# Debug.net
KiCad netlist of a schematic drawn in Altium Designer
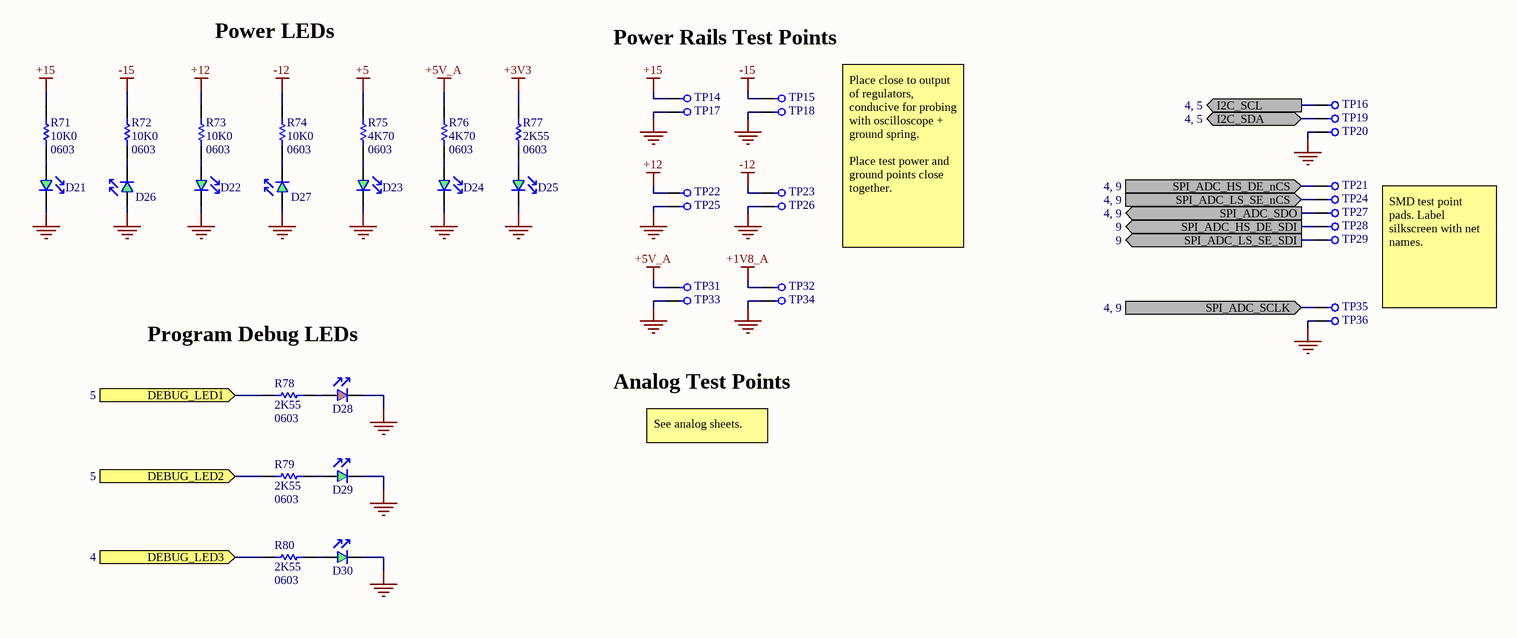
[diagram p0: Debug.SchDoc]

(export (version "E")
  (design (tool "Eeschema 10.0.6"))
  (components
    (comp (ref "D21")
      (value "LED Green")
      (footprint "0603 LED")
      (description "Generic Green LED")
      (libsource (lib "MRT SCH Library") (part "LED Green"))
    )
    (comp (ref "D22")
      (value "LED Green")
      (footprint "0603 LED")
      (description "Generic Green LED")
      (libsource (lib "MRT SCH Library") (part "LED Green"))
    )
    (comp (ref "D23")
      (value "LED Green")
      (footprint "0603 LED")
      (description "Generic Green LED")
      (libsource (lib "MRT SCH Library") (part "LED Green"))
    )
    (comp (ref "D24")
      (value "LED Green")
      (footprint "0603 LED")
      (description "Generic Green LED")
      (libsource (lib "MRT SCH Library") (part "LED Green"))
    )
    (comp (ref "D25")
      (value "LED Green")
      (footprint "0603 LED")
      (description "Generic Green LED")
      (libsource (lib "MRT SCH Library") (part "LED Green"))
    )
    (comp (ref "D26")
      (value "LED Green")
      (footprint "0603 LED")
      (description "Generic Green LED")
      (libsource (lib "MRT SCH Library") (part "LED Green"))
    )
    (comp (ref "D27")
      (value "LED Green")
      (footprint "0603 LED")
      (description "Generic Green LED")
      (libsource (lib "MRT SCH Library") (part "LED Green"))
    )
    (comp (ref "D28")
      (value "LED Red")
      (footprint "0603 LED")
      (description "Generic Red LED")
      (libsource (lib "MRT SCH Library") (part "LED Red"))
    )
    (comp (ref "D29")
      (value "LED Green")
      (footprint "0603 LED")
      (description "Generic Green LED")
      (libsource (lib "MRT SCH Library") (part "LED Green"))
    )
    (comp (ref "D30")
      (value "LED Green")
      (footprint "0603 LED")
      (description "Generic Green LED")
      (libsource (lib "MRT SCH Library") (part "LED Green"))
    )
    (comp (ref "R71")
      (value "10K0")
      (footprint "0603 RES")
      (description "Resistor")
      (fields (field (name "ALTIUM_VALUE") "0603") (field (name "PUBLISHER") "Altium Limited"))
      (libsource (lib "Miscellaneous Devices") (part "Res1"))
    )
    (comp (ref "R72")
      (value "10K0")
      (footprint "0603 RES")
      (description "Resistor")
      (fields (field (name "ALTIUM_VALUE") "0603") (field (name "PUBLISHER") "Altium Limited"))
      (libsource (lib "Miscellaneous Devices") (part "Res1"))
    )
    (comp (ref "R73")
      (value "10K0")
      (footprint "0603 RES")
      (description "Resistor")
      (fields (field (name "ALTIUM_VALUE") "0603") (field (name "PUBLISHER") "Altium Limited"))
      (libsource (lib "Miscellaneous Devices") (part "Res1"))
    )
    (comp (ref "R74")
      (value "10K0")
      (footprint "0603 RES")
      (description "Resistor")
      (fields (field (name "ALTIUM_VALUE") "0603") (field (name "PUBLISHER") "Altium Limited"))
      (libsource (lib "Miscellaneous Devices") (part "Res1"))
    )
    (comp (ref "R75")
      (value "4K70")
      (footprint "0603 RES")
      (description "Resistor")
      (fields (field (name "ALTIUM_VALUE") "0603") (field (name "PUBLISHER") "Altium Limited"))
      (libsource (lib "Miscellaneous Devices") (part "Res1"))
    )
    (comp (ref "R76")
      (value "4K70")
      (footprint "0603 RES")
      (description "Resistor")
      (fields (field (name "ALTIUM_VALUE") "0603") (field (name "PUBLISHER") "Altium Limited"))
      (libsource (lib "Miscellaneous Devices") (part "Res1"))
    )
    (comp (ref "R77")
      (value "2K55")
      (footprint "0603 RES")
      (description "Resistor")
      (fields (field (name "ALTIUM_VALUE") "0603") (field (name "PUBLISHER") "Altium Limited"))
      (libsource (lib "Miscellaneous Devices") (part "Res1"))
    )
    (comp (ref "R78")
      (value "2K55")
      (footprint "0603 RES")
      (description "Resistor")
      (fields (field (name "ALTIUM_VALUE") "0603") (field (name "PUBLISHER") "Altium Limited"))
      (libsource (lib "Miscellaneous Devices") (part "Res1"))
    )
    (comp (ref "R79")
      (value "2K55")
      (footprint "0603 RES")
      (description "Resistor")
      (fields (field (name "ALTIUM_VALUE") "0603") (field (name "PUBLISHER") "Altium Limited"))
      (libsource (lib "Miscellaneous Devices") (part "Res1"))
    )
    (comp (ref "R80")
      (value "2K55")
      (footprint "0603 RES")
      (description "Resistor")
      (fields (field (name "ALTIUM_VALUE") "0603") (field (name "PUBLISHER") "Altium Limited"))
      (libsource (lib "Miscellaneous Devices") (part "Res1"))
    )
    (comp (ref "TP14")
      (value "Test Point")
      (footprint "Test Point Keystone 5015")
      (description "Keystone 5015 Test point")
      (libsource (lib "MRT SCH Library") (part "Test Point"))
    )
    (comp (ref "TP15")
      (value "Test Point")
      (footprint "Test Point Keystone 5015")
      (description "Keystone 5015 Test point")
      (libsource (lib "MRT SCH Library") (part "Test Point"))
    )
    (comp (ref "TP16")
      (value "Test Point")
      (footprint "TEST POINT SMD PAD")
      (description "Keystone 5015 Test point")
      (libsource (lib "MRT SCH Library") (part "Test Point"))
    )
    (comp (ref "TP17")
      (value "Test Point")
      (footprint "Test Point Keystone 5015")
      (description "Keystone 5015 Test point")
      (libsource (lib "MRT SCH Library") (part "Test Point"))
    )
    (comp (ref "TP18")
      (value "Test Point")
      (footprint "Test Point Keystone 5015")
      (description "Keystone 5015 Test point")
      (libsource (lib "MRT SCH Library") (part "Test Point"))
    )
    (comp (ref "TP19")
      (value "Test Point")
      (footprint "TEST POINT SMD PAD")
      (description "Keystone 5015 Test point")
      (libsource (lib "MRT SCH Library") (part "Test Point"))
    )
    (comp (ref "TP20")
      (value "Test Point")
      (footprint "TEST POINT SMD PAD")
      (description "Keystone 5015 Test point")
      (libsource (lib "MRT SCH Library") (part "Test Point"))
    )
    (comp (ref "TP21")
      (value "Test Point")
      (footprint "TEST POINT SMD PAD")
      (description "Keystone 5015 Test point")
      (libsource (lib "MRT SCH Library") (part "Test Point"))
    )
    (comp (ref "TP22")
      (value "Test Point")
      (footprint "Test Point Keystone 5015")
      (description "Keystone 5015 Test point")
      (libsource (lib "MRT SCH Library") (part "Test Point"))
    )
    (comp (ref "TP23")
      (value "Test Point")
      (footprint "Test Point Keystone 5015")
      (description "Keystone 5015 Test point")
      (libsource (lib "MRT SCH Library") (part "Test Point"))
    )
    (comp (ref "TP24")
      (value "Test Point")
      (footprint "TEST POINT SMD PAD")
      (description "Keystone 5015 Test point")
      (libsource (lib "MRT SCH Library") (part "Test Point"))
    )
    (comp (ref "TP25")
      (value "Test Point")
      (footprint "Test Point Keystone 5015")
      (description "Keystone 5015 Test point")
      (libsource (lib "MRT SCH Library") (part "Test Point"))
    )
    (comp (ref "TP26")
      (value "Test Point")
      (footprint "Test Point Keystone 5015")
      (description "Keystone 5015 Test point")
      (libsource (lib "MRT SCH Library") (part "Test Point"))
    )
    (comp (ref "TP27")
      (value "Test Point")
      (footprint "TEST POINT SMD PAD")
      (description "Keystone 5015 Test point")
      (libsource (lib "MRT SCH Library") (part "Test Point"))
    )
    (comp (ref "TP28")
      (value "Test Point")
      (footprint "TEST POINT SMD PAD")
      (description "Keystone 5015 Test point")
      (libsource (lib "MRT SCH Library") (part "Test Point"))
    )
    (comp (ref "TP29")
      (value "Test Point")
      (footprint "TEST POINT SMD PAD")
      (description "Keystone 5015 Test point")
      (libsource (lib "MRT SCH Library") (part "Test Point"))
    )
    (comp (ref "TP31")
      (value "Test Point")
      (footprint "Test Point Keystone 5015")
      (description "Keystone 5015 Test point")
      (libsource (lib "MRT SCH Library") (part "Test Point"))
    )
    (comp (ref "TP32")
      (value "Test Point")
      (footprint "Test Point Keystone 5015")
      (description "Keystone 5015 Test point")
      (libsource (lib "MRT SCH Library") (part "Test Point"))
    )
    (comp (ref "TP33")
      (value "Test Point")
      (footprint "Test Point Keystone 5015")
      (description "Keystone 5015 Test point")
      (libsource (lib "MRT SCH Library") (part "Test Point"))
    )
    (comp (ref "TP34")
      (value "Test Point")
      (footprint "Test Point Keystone 5015")
      (description "Keystone 5015 Test point")
      (libsource (lib "MRT SCH Library") (part "Test Point"))
    )
    (comp (ref "TP35")
      (value "Test Point")
      (footprint "TEST POINT SMD PAD")
      (description "Keystone 5015 Test point")
      (libsource (lib "MRT SCH Library") (part "Test Point"))
    )
    (comp (ref "TP36")
      (value "Test Point")
      (footprint "TEST POINT SMD PAD")
      (description "Keystone 5015 Test point")
      (libsource (lib "MRT SCH Library") (part "Test Point"))
    )
  )
  (nets
    (net (code "1") (name "+1V8_A") (class "Default")
      (node (ref "TP32") (pin "1") (pinfunction "1_1") (pintype "passive"))
    )
    (net (code "2") (name "+3V3") (class "Default")
      (node (ref "R77") (pin "2") (pinfunction "2_2") (pintype "passive"))
    )
    (net (code "3") (name "+5") (class "Default")
      (node (ref "R75") (pin "2") (pinfunction "2_2") (pintype "passive"))
    )
    (net (code "4") (name "+5V_A") (class "Default")
      (node (ref "R76") (pin "2") (pinfunction "2_2") (pintype "passive"))
      (node (ref "TP31") (pin "1") (pinfunction "1_1") (pintype "passive"))
    )
    (net (code "5") (name "+12") (class "Default")
      (node (ref "R73") (pin "2") (pinfunction "2_2") (pintype "passive"))
      (node (ref "TP22") (pin "1") (pinfunction "1_1") (pintype "passive"))
    )
    (net (code "6") (name "+15") (class "Default")
      (node (ref "R71") (pin "2") (pinfunction "2_2") (pintype "passive"))
      (node (ref "TP14") (pin "1") (pinfunction "1_1") (pintype "passive"))
    )
    (net (code "7") (name "-12") (class "Default")
      (node (ref "R74") (pin "2") (pinfunction "2_2") (pintype "passive"))
      (node (ref "TP23") (pin "1") (pinfunction "1_1") (pintype "passive"))
    )
    (net (code "8") (name "-15") (class "Default")
      (node (ref "R72") (pin "2") (pinfunction "2_2") (pintype "passive"))
      (node (ref "TP15") (pin "1") (pinfunction "1_1") (pintype "passive"))
    )
    (net (code "9") (name "/DEBUG_LED1") (class "Default")
      (node (ref "R78") (pin "2") (pinfunction "2_2") (pintype "passive"))
    )
    (net (code "10") (name "/DEBUG_LED2") (class "Default")
      (node (ref "R79") (pin "2") (pinfunction "2_2") (pintype "passive"))
    )
    (net (code "11") (name "/DEBUG_LED3") (class "Default")
      (node (ref "R80") (pin "2") (pinfunction "2_2") (pintype "passive"))
    )
    (net (code "12") (name "/I2C_SCL") (class "Default")
      (node (ref "TP16") (pin "1") (pinfunction "1_1") (pintype "passive"))
    )
    (net (code "13") (name "/I2C_SDA") (class "Default")
      (node (ref "TP19") (pin "1") (pinfunction "1_1") (pintype "passive"))
    )
    (net (code "14") (name "/SPI_ADC_HS_DE_SDI") (class "Default")
      (node (ref "TP28") (pin "1") (pinfunction "1_1") (pintype "passive"))
    )
    (net (code "15") (name "/SPI_ADC_HS_DE_nCS") (class "Default")
      (node (ref "TP21") (pin "1") (pinfunction "1_1") (pintype "passive"))
    )
    (net (code "16") (name "/SPI_ADC_LS_SE_SDI") (class "Default")
      (node (ref "TP29") (pin "1") (pinfunction "1_1") (pintype "passive"))
    )
    (net (code "17") (name "/SPI_ADC_LS_SE_nCS") (class "Default")
      (node (ref "TP24") (pin "1") (pinfunction "1_1") (pintype "passive"))
    )
    (net (code "18") (name "/SPI_ADC_SCLK") (class "Default")
      (node (ref "TP35") (pin "1") (pinfunction "1_1") (pintype "passive"))
    )
    (net (code "19") (name "/SPI_ADC_SDO") (class "Default")
      (node (ref "TP27") (pin "1") (pinfunction "1_1") (pintype "passive"))
    )
    (net (code "20") (name "GND") (class "Default")
      (node (ref "D21") (pin "2") (pinfunction "Cathode_2") (pintype "passive"))
      (node (ref "D22") (pin "2") (pinfunction "Cathode_2") (pintype "passive"))
      (node (ref "D23") (pin "2") (pinfunction "Cathode_2") (pintype "passive"))
      (node (ref "D24") (pin "2") (pinfunction "Cathode_2") (pintype "passive"))
      (node (ref "D25") (pin "2") (pinfunction "Cathode_2") (pintype "passive"))
      (node (ref "D26") (pin "1") (pinfunction "Anode_1") (pintype "passive"))
      (node (ref "D27") (pin "1") (pinfunction "Anode_1") (pintype "passive"))
      (node (ref "D28") (pin "2") (pinfunction "Cathode_2") (pintype "passive"))
      (node (ref "D29") (pin "2") (pinfunction "Cathode_2") (pintype "passive"))
      (node (ref "D30") (pin "2") (pinfunction "Cathode_2") (pintype "passive"))
      (node (ref "TP17") (pin "1") (pinfunction "1_1") (pintype "passive"))
      (node (ref "TP18") (pin "1") (pinfunction "1_1") (pintype "passive"))
      (node (ref "TP20") (pin "1") (pinfunction "1_1") (pintype "passive"))
      (node (ref "TP25") (pin "1") (pinfunction "1_1") (pintype "passive"))
      (node (ref "TP26") (pin "1") (pinfunction "1_1") (pintype "passive"))
      (node (ref "TP33") (pin "1") (pinfunction "1_1") (pintype "passive"))
      (node (ref "TP34") (pin "1") (pinfunction "1_1") (pintype "passive"))
      (node (ref "TP36") (pin "1") (pinfunction "1_1") (pintype "passive"))
    )
    (net (code "21") (name "Net-(D21-Anode)") (class "Default")
      (node (ref "D21") (pin "1") (pinfunction "Anode_1") (pintype "passive"))
      (node (ref "R71") (pin "1") (pinfunction "1_1") (pintype "passive"))
    )
    (net (code "22") (name "Net-(D22-Anode)") (class "Default")
      (node (ref "D22") (pin "1") (pinfunction "Anode_1") (pintype "passive"))
      (node (ref "R73") (pin "1") (pinfunction "1_1") (pintype "passive"))
    )
    (net (code "23") (name "Net-(D23-Anode)") (class "Default")
      (node (ref "D23") (pin "1") (pinfunction "Anode_1") (pintype "passive"))
      (node (ref "R75") (pin "1") (pinfunction "1_1") (pintype "passive"))
    )
    (net (code "24") (name "Net-(D24-Anode)") (class "Default")
      (node (ref "D24") (pin "1") (pinfunction "Anode_1") (pintype "passive"))
      (node (ref "R76") (pin "1") (pinfunction "1_1") (pintype "passive"))
    )
    (net (code "25") (name "Net-(D25-Anode)") (class "Default")
      (node (ref "D25") (pin "1") (pinfunction "Anode_1") (pintype "passive"))
      (node (ref "R77") (pin "1") (pinfunction "1_1") (pintype "passive"))
    )
    (net (code "26") (name "Net-(D26-Cathode)") (class "Default")
      (node (ref "D26") (pin "2") (pinfunction "Cathode_2") (pintype "passive"))
      (node (ref "R72") (pin "1") (pinfunction "1_1") (pintype "passive"))
    )
    (net (code "27") (name "Net-(D27-Cathode)") (class "Default")
      (node (ref "D27") (pin "2") (pinfunction "Cathode_2") (pintype "passive"))
      (node (ref "R74") (pin "1") (pinfunction "1_1") (pintype "passive"))
    )
    (net (code "28") (name "Net-(D28-Anode)") (class "Default")
      (node (ref "D28") (pin "1") (pinfunction "Anode_1") (pintype "passive"))
      (node (ref "R78") (pin "1") (pinfunction "1_1") (pintype "passive"))
    )
    (net (code "29") (name "Net-(D29-Anode)") (class "Default")
      (node (ref "D29") (pin "1") (pinfunction "Anode_1") (pintype "passive"))
      (node (ref "R79") (pin "1") (pinfunction "1_1") (pintype "passive"))
    )
    (net (code "30") (name "Net-(D30-Anode)") (class "Default")
      (node (ref "D30") (pin "1") (pinfunction "Anode_1") (pintype "passive"))
      (node (ref "R80") (pin "1") (pinfunction "1_1") (pintype "passive"))
    )
  )
)
